# blnkbrd.net
KiCad netlist of a schematic drawn in EAGLE
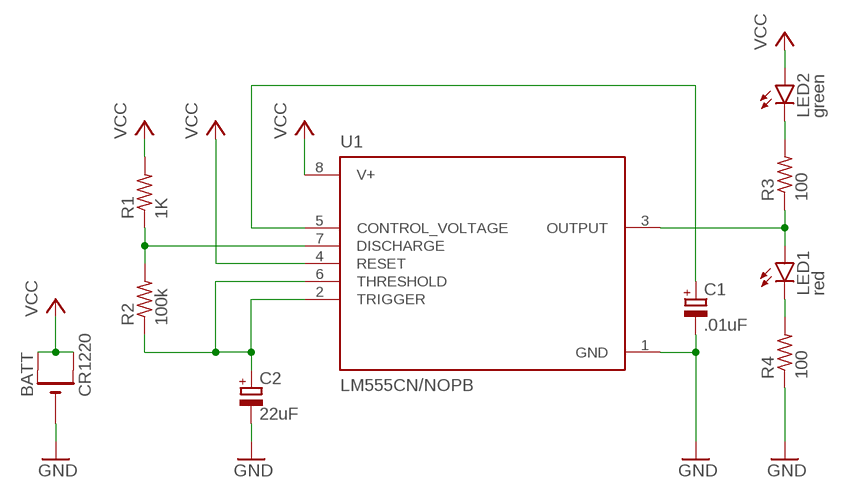
[diagram p0: schematic, sheet 1]

(export (version "E")
  (design (tool "Eeschema 10.0.6"))
  (components
    (comp (ref "BATT")
      (value "CR1220")
      (footprint "eagle-import:CR1220-SMD")
      (libsource (lib "eagle-import") (part "CR1220SMT"))
    )
    (comp (ref "C1")
      (value ".01uF")
      (footprint "eagle-import:E2,5-6E")
      (libsource (lib "eagle-import") (part "CPOL-EUE2,5-6E"))
    )
    (comp (ref "C2")
      (value "22uF")
      (footprint "eagle-import:E2,5-6E")
      (libsource (lib "eagle-import") (part "CPOL-EUE2,5-6E"))
    )
    (comp (ref "LED1")
      (value "red")
      (footprint "eagle-import:LED3MM")
      (libsource (lib "eagle-import") (part "LED3MM"))
    )
    (comp (ref "LED2")
      (value "green")
      (footprint "eagle-import:LED3MM")
      (libsource (lib "eagle-import") (part "LED3MM"))
    )
    (comp (ref "R1")
      (value "1K")
      (footprint "eagle-import:0207_10")
      (libsource (lib "eagle-import") (part "R-US_0207/10"))
    )
    (comp (ref "R2")
      (value "100k")
      (footprint "eagle-import:0207_10")
      (libsource (lib "eagle-import") (part "R-US_0207/10"))
    )
    (comp (ref "R3")
      (value "100")
      (footprint "eagle-import:0207_10")
      (libsource (lib "eagle-import") (part "R-US_0207/10"))
    )
    (comp (ref "R4")
      (value "100")
      (footprint "eagle-import:0207_10")
      (libsource (lib "eagle-import") (part "R-US_0207/10"))
    )
    (comp (ref "U1")
      (value "LM555CN/NOPB")
      (footprint "eagle-import:DIP794W45P254L959H508Q8")
      (fields (field (name "MF") "Texas Instruments"))
      (libsource (lib "eagle-import") (part "LM555CN/NOPB"))
    )
  )
  (nets
    (net (code "1") (name "GND") (class "Default")
      (node (ref "BATT") (pin "-") (pinfunction "-_-") (pintype "passive"))
      (node (ref "C1") (pin "-") (pinfunction "-_-") (pintype "passive"))
      (node (ref "C2") (pin "-") (pinfunction "-_-") (pintype "passive"))
      (node (ref "R4") (pin "1") (pinfunction "1_1") (pintype "passive"))
      (node (ref "U1") (pin "1") (pinfunction "GND_1") (pintype "power_in"))
    )
    (net (code "2") (name "Net-(LED1-C)") (class "Default")
      (node (ref "LED1") (pin "K") (pinfunction "C_K") (pintype "passive"))
      (node (ref "R4") (pin "2") (pinfunction "2_2") (pintype "passive"))
    )
    (net (code "3") (name "Net-(LED2-C)") (class "Default")
      (node (ref "LED2") (pin "K") (pinfunction "C_K") (pintype "passive"))
      (node (ref "R3") (pin "2") (pinfunction "2_2") (pintype "passive"))
    )
    (net (code "4") (name "Net-(U1-CONTROL_VOLTAGE)") (class "Default")
      (node (ref "C1") (pin "+") (pinfunction "+_+") (pintype "passive"))
      (node (ref "U1") (pin "5") (pinfunction "CONTROL_VOLTAGE_5") (pintype "input"))
    )
    (net (code "5") (name "Net-(U1-DISCHARGE)") (class "Default")
      (node (ref "R1") (pin "1") (pinfunction "1_1") (pintype "passive"))
      (node (ref "R2") (pin "2") (pinfunction "2_2") (pintype "passive"))
      (node (ref "U1") (pin "7") (pinfunction "DISCHARGE_7") (pintype "input"))
    )
    (net (code "6") (name "Net-(U1-OUTPUT)") (class "Default")
      (node (ref "LED1") (pin "A") (pinfunction "A_A") (pintype "passive"))
      (node (ref "R3") (pin "1") (pinfunction "1_1") (pintype "passive"))
      (node (ref "U1") (pin "3") (pinfunction "OUTPUT_3") (pintype "output"))
    )
    (net (code "7") (name "Net-(U1-THRESHOLD)") (class "Default")
      (node (ref "C2") (pin "+") (pinfunction "+_+") (pintype "passive"))
      (node (ref "R2") (pin "1") (pinfunction "1_1") (pintype "passive"))
      (node (ref "U1") (pin "2") (pinfunction "TRIGGER_2") (pintype "input"))
      (node (ref "U1") (pin "6") (pinfunction "THRESHOLD_6") (pintype "input"))
    )
    (net (code "8") (name "VCC") (class "Default")
      (node (ref "BATT") (pin "+$1") (pinfunction "+_+$1") (pintype "passive"))
      (node (ref "BATT") (pin "+$2") (pinfunction "+1_+$2") (pintype "passive"))
      (node (ref "LED2") (pin "A") (pinfunction "A_A") (pintype "passive"))
      (node (ref "R1") (pin "2") (pinfunction "2_2") (pintype "passive"))
      (node (ref "U1") (pin "4") (pinfunction "RESET_4") (pintype "input"))
      (node (ref "U1") (pin "8") (pinfunction "V+_8") (pintype "power_in"))
    )
  )
)
